# d11_usb_std.net
KiCad netlist of a schematic drawn in EAGLE
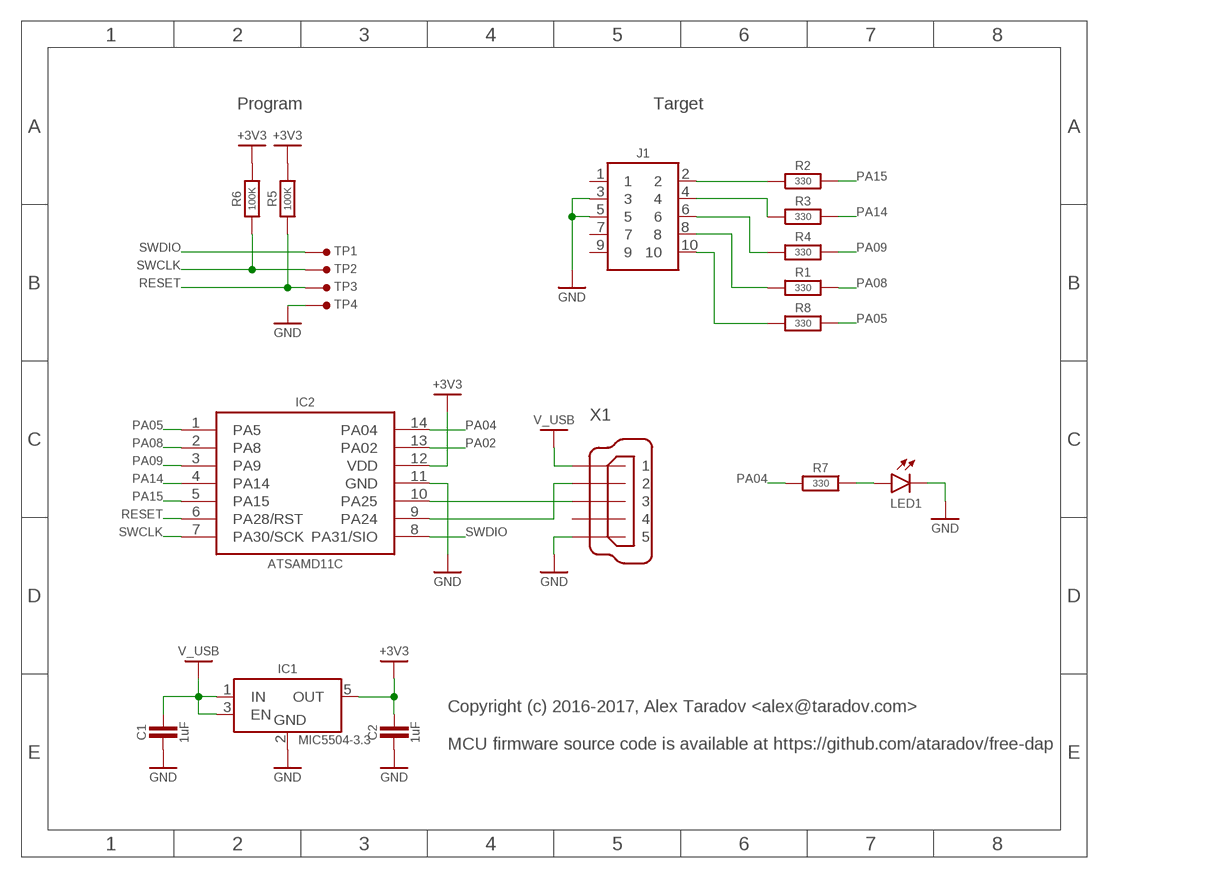
[diagram p0: schematic, sheet 1]

(export (version "E")
  (design (tool "Eeschema 10.0.6"))
  (components
    (comp (ref "C1")
      (value "1uF")
      (footprint "eagle-import:SMD0603")
      (libsource (lib "eagle-import") (part "C-0603"))
    )
    (comp (ref "C2")
      (value "1uF")
      (footprint "eagle-import:SMD0603")
      (libsource (lib "eagle-import") (part "C-0603"))
    )
    (comp (ref "IC1")
      (value "MIC5504-3.3")
      (footprint "eagle-import:SOT23-5")
      (libsource (lib "eagle-import") (part "MIC5504-SOT23-5"))
    )
    (comp (ref "IC2")
      (value "ATSAMD11C")
      (footprint "eagle-import:SO-14")
      (libsource (lib "eagle-import") (part "ATSAMD11C"))
    )
    (comp (ref "J1")
      (value "HEADER-5X2-TH-1.27")
      (footprint "eagle-import:HEADER-5X2-1.27MM")
      (libsource (lib "eagle-import") (part "HEADER-5X2-TH-1.27"))
    )
    (comp (ref "LED1")
      (value "LED_SMDLED_0603")
      (footprint "eagle-import:SMD0603")
      (libsource (lib "eagle-import") (part "LED_SMDLED_0603"))
    )
    (comp (ref "R1")
      (value "330")
      (footprint "eagle-import:SMD0603")
      (libsource (lib "eagle-import") (part "R-0603"))
    )
    (comp (ref "R2")
      (value "330")
      (footprint "eagle-import:SMD0603")
      (libsource (lib "eagle-import") (part "R-0603"))
    )
    (comp (ref "R3")
      (value "330")
      (footprint "eagle-import:SMD0603")
      (libsource (lib "eagle-import") (part "R-0603"))
    )
    (comp (ref "R4")
      (value "330")
      (footprint "eagle-import:SMD0603")
      (libsource (lib "eagle-import") (part "R-0603"))
    )
    (comp (ref "R5")
      (value "100K")
      (footprint "eagle-import:SMD0603")
      (libsource (lib "eagle-import") (part "R-0603"))
    )
    (comp (ref "R6")
      (value "100K")
      (footprint "eagle-import:SMD0603")
      (libsource (lib "eagle-import") (part "R-0603"))
    )
    (comp (ref "R7")
      (value "330")
      (footprint "eagle-import:SMD0603")
      (libsource (lib "eagle-import") (part "R-0603"))
    )
    (comp (ref "R8")
      (value "330")
      (footprint "eagle-import:SMD0603")
      (libsource (lib "eagle-import") (part "R-0603"))
    )
    (comp (ref "TP1")
      (value "SIO")
      (footprint "eagle-import:TP-1.27MM")
      (libsource (lib "eagle-import") (part "TEST-POINT-1.27MM"))
    )
    (comp (ref "TP2")
      (value "TEST-POINT-1.27MM")
      (footprint "eagle-import:TP-1.27MM")
      (libsource (lib "eagle-import") (part "TEST-POINT-1.27MM"))
    )
    (comp (ref "TP3")
      (value "TEST-POINT-1.27MM")
      (footprint "eagle-import:TP-1.27MM")
      (libsource (lib "eagle-import") (part "TEST-POINT-1.27MM"))
    )
    (comp (ref "TP4")
      (value "TEST-POINT-1.27MM")
      (footprint "eagle-import:TP-1.27MM")
      (libsource (lib "eagle-import") (part "TEST-POINT-1.27MM"))
    )
    (comp (ref "X1")
      (value "MINI-USB-32005-201")
      (footprint "eagle-import:32005-201")
      (libsource (lib "eagle-import") (part "MINI-USB-32005-201"))
    )
  )
  (nets
    (net (code "1") (name "+3V3") (class "Default")
      (node (ref "C2") (pin "2") (pinfunction "2_2") (pintype "passive"))
      (node (ref "IC1") (pin "5") (pinfunction "OUT_5") (pintype "power_in"))
      (node (ref "IC2") (pin "12") (pinfunction "VDD_12") (pintype "bidirectional"))
      (node (ref "R5") (pin "2") (pinfunction "2_2") (pintype "passive"))
      (node (ref "R6") (pin "2") (pinfunction "2_2") (pintype "passive"))
    )
    (net (code "2") (name "/PA02") (class "Default")
      (node (ref "IC2") (pin "13") (pinfunction "PA02_13") (pintype "bidirectional"))
    )
    (net (code "3") (name "/PA04") (class "Default")
      (node (ref "IC2") (pin "14") (pinfunction "PA04_14") (pintype "bidirectional"))
      (node (ref "R7") (pin "1") (pinfunction "1_1") (pintype "passive"))
    )
    (net (code "4") (name "/PA05") (class "Default")
      (node (ref "IC2") (pin "1") (pinfunction "PA5_1") (pintype "bidirectional"))
      (node (ref "R8") (pin "2") (pinfunction "2_2") (pintype "passive"))
    )
    (net (code "5") (name "/PA08") (class "Default")
      (node (ref "IC2") (pin "2") (pinfunction "PA8_2") (pintype "bidirectional"))
      (node (ref "R1") (pin "2") (pinfunction "2_2") (pintype "passive"))
    )
    (net (code "6") (name "/PA09") (class "Default")
      (node (ref "IC2") (pin "3") (pinfunction "PA9_3") (pintype "bidirectional"))
      (node (ref "R4") (pin "2") (pinfunction "2_2") (pintype "passive"))
    )
    (net (code "7") (name "/PA14") (class "Default")
      (node (ref "IC2") (pin "4") (pinfunction "PA14_4") (pintype "bidirectional"))
      (node (ref "R3") (pin "2") (pinfunction "2_2") (pintype "passive"))
    )
    (net (code "8") (name "/PA15") (class "Default")
      (node (ref "IC2") (pin "5") (pinfunction "PA15_5") (pintype "bidirectional"))
      (node (ref "R2") (pin "2") (pinfunction "2_2") (pintype "passive"))
    )
    (net (code "9") (name "/RESET") (class "Default")
      (node (ref "IC2") (pin "6") (pinfunction "PA28/RST_6") (pintype "bidirectional"))
      (node (ref "R5") (pin "1") (pinfunction "1_1") (pintype "passive"))
      (node (ref "TP3") (pin "1") (pinfunction "1_1") (pintype "passive"))
    )
    (net (code "10") (name "/SWCLK") (class "Default")
      (node (ref "IC2") (pin "7") (pinfunction "PA30/SCK_7") (pintype "bidirectional"))
      (node (ref "R6") (pin "1") (pinfunction "1_1") (pintype "passive"))
      (node (ref "TP2") (pin "1") (pinfunction "1_1") (pintype "passive"))
    )
    (net (code "11") (name "/SWDIO") (class "Default")
      (node (ref "IC2") (pin "8") (pinfunction "PA31/SIO_8") (pintype "bidirectional"))
      (node (ref "TP1") (pin "1") (pinfunction "1_1") (pintype "passive"))
    )
    (net (code "12") (name "GND") (class "Default")
      (node (ref "C1") (pin "1") (pinfunction "1_1") (pintype "passive"))
      (node (ref "C2") (pin "1") (pinfunction "1_1") (pintype "passive"))
      (node (ref "IC1") (pin "2") (pinfunction "GND_2") (pintype "power_in"))
      (node (ref "IC2") (pin "11") (pinfunction "GND_11") (pintype "bidirectional"))
      (node (ref "J1") (pin "3") (pinfunction "3_3") (pintype "passive"))
      (node (ref "J1") (pin "5") (pinfunction "5_5") (pintype "passive"))
      (node (ref "LED1") (pin "2") (pinfunction "C_2") (pintype "passive"))
      (node (ref "TP4") (pin "1") (pinfunction "1_1") (pintype "passive"))
      (node (ref "X1") (pin "5") (pinfunction "5_5") (pintype "passive"))
    )
    (net (code "13") (name "Net-(IC2-PA24)") (class "Default")
      (node (ref "IC2") (pin "9") (pinfunction "PA24_9") (pintype "bidirectional"))
      (node (ref "X1") (pin "2") (pinfunction "2_2") (pintype "passive"))
    )
    (net (code "14") (name "Net-(IC2-PA25)") (class "Default")
      (node (ref "IC2") (pin "10") (pinfunction "PA25_10") (pintype "bidirectional"))
      (node (ref "X1") (pin "3") (pinfunction "3_3") (pintype "passive"))
    )
    (net (code "15") (name "Net-(J1-Pad2)") (class "Default")
      (node (ref "J1") (pin "2") (pinfunction "2_2") (pintype "passive"))
      (node (ref "R2") (pin "1") (pinfunction "1_1") (pintype "passive"))
    )
    (net (code "16") (name "Net-(J1-Pad4)") (class "Default")
      (node (ref "J1") (pin "4") (pinfunction "4_4") (pintype "passive"))
      (node (ref "R3") (pin "1") (pinfunction "1_1") (pintype "passive"))
    )
    (net (code "17") (name "Net-(J1-Pad6)") (class "Default")
      (node (ref "J1") (pin "6") (pinfunction "6_6") (pintype "passive"))
      (node (ref "R4") (pin "1") (pinfunction "1_1") (pintype "passive"))
    )
    (net (code "18") (name "Net-(J1-Pad8)") (class "Default")
      (node (ref "J1") (pin "8") (pinfunction "8_8") (pintype "passive"))
      (node (ref "R1") (pin "1") (pinfunction "1_1") (pintype "passive"))
    )
    (net (code "19") (name "Net-(J1-Pad10)") (class "Default")
      (node (ref "J1") (pin "10") (pinfunction "10_10") (pintype "passive"))
      (node (ref "R8") (pin "1") (pinfunction "1_1") (pintype "passive"))
    )
    (net (code "20") (name "Net-(LED1-A)") (class "Default")
      (node (ref "LED1") (pin "1") (pinfunction "A_1") (pintype "passive"))
      (node (ref "R7") (pin "2") (pinfunction "2_2") (pintype "passive"))
    )
    (net (code "21") (name "V_USB") (class "Default")
      (node (ref "C1") (pin "2") (pinfunction "2_2") (pintype "passive"))
      (node (ref "IC1") (pin "1") (pinfunction "IN_1") (pintype "power_in"))
      (node (ref "IC1") (pin "3") (pinfunction "EN_3") (pintype "input"))
      (node (ref "X1") (pin "1") (pinfunction "1_1") (pintype "passive"))
    )
    (net (code "22") (name "unconnected-(J1-Pad1)") (class "Default")
      (node (ref "J1") (pin "1") (pinfunction "1_1") (pintype "passive"))
    )
    (net (code "23") (name "unconnected-(J1-Pad7)") (class "Default")
      (node (ref "J1") (pin "7") (pinfunction "7_7") (pintype "passive"))
    )
    (net (code "24") (name "unconnected-(J1-Pad9)") (class "Default")
      (node (ref "J1") (pin "9") (pinfunction "9_9") (pintype "passive"))
    )
    (net (code "25") (name "unconnected-(X1-Pad4)") (class "Default")
      (node (ref "X1") (pin "4") (pinfunction "4_4") (pintype "passive"))
    )
  )
)
